# Intelligent_Agriculture.net
KiCad netlist of a schematic drawn in Altium Designer
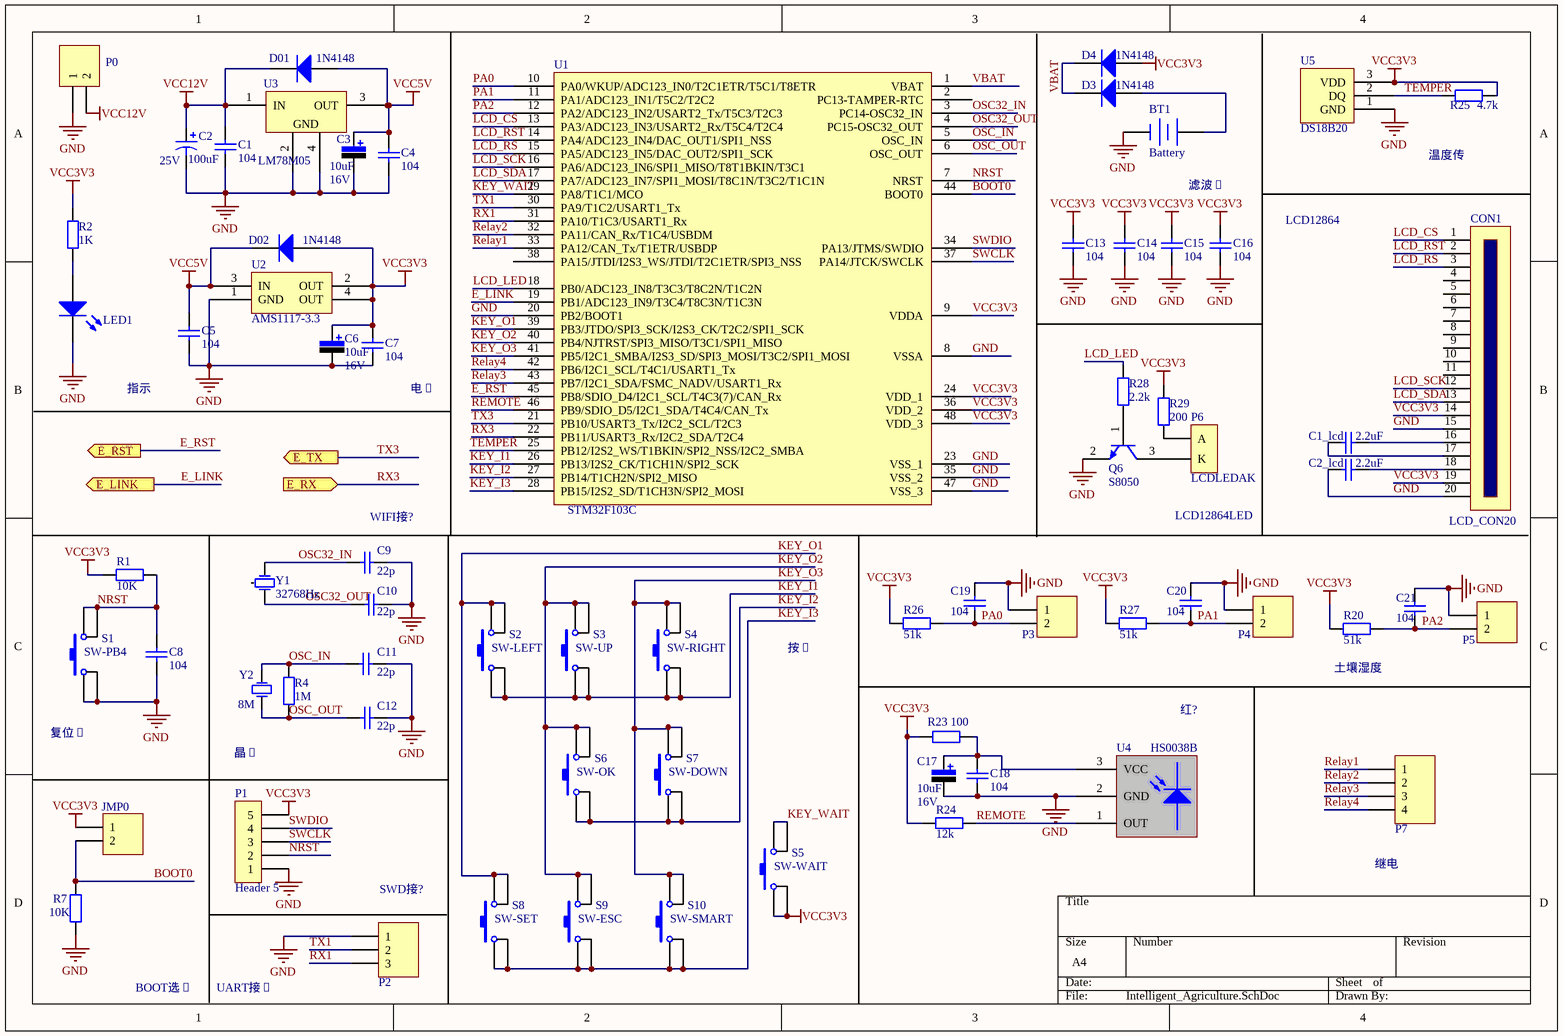
[diagram p0: Intelligent_Agriculture.SchDoc]

(export (version "E")
  (design (tool "Eeschema 10.0.6"))
  (components
    (comp (ref "BT1") (value "Battery") (description "备份电池") (libsource (lib "fszhang") (part "Battery")))
    (comp (ref "C1")
      (value "104")
      (footprint "C-RAD-0805")
      (description "无极性电容")
      (fields (field (name "Comment") "Cap"))
      (libsource (lib "Intelligent_Agriculture_Lib") (part "Cap"))
    )
    (comp (ref "C1_lcd")
      (value "2.2uF")
      (footprint "C-RAD-0805")
      (description "无极性电容")
      (fields (field (name "Comment") "Cap"))
      (libsource (lib "Intelligent_Agriculture_Lib") (part "Cap"))
    )
    (comp (ref "C2")
      (value "100uF")
      (footprint "C-RB-2.54")
      (description "电解电容")
      (fields (field (name "VOL") "25V") (field (name "Comment") "Cap Pol1"))
      (libsource (lib "Miscellaneous Devices") (part "Cap Pol1"))
    )
    (comp (ref "C2_lcd")
      (value "2.2uF")
      (footprint "C-RAD-0805")
      (description "无极性电容")
      (fields (field (name "Comment") "Cap"))
      (libsource (lib "Intelligent_Agriculture_Lib") (part "Cap"))
    )
    (comp (ref "C3")
      (value "10uF")
      (footprint "CAP-3528")
      (description "钽电容")
      (fields (field (name "VOL") "16V") (field (name "Comment") "Cap Pol"))
      (libsource (lib "Intelligent_Agriculture_Lib") (part "Cap Pol"))
    )
    (comp (ref "C4")
      (value "104")
      (footprint "C-RAD-0805")
      (description "无极性电容")
      (fields (field (name "Comment") "Cap"))
      (libsource (lib "Intelligent_Agriculture_Lib") (part "Cap"))
    )
    (comp (ref "C5")
      (value "104")
      (footprint "C-RAD-0805")
      (description "无极性电容")
      (fields (field (name "Comment") "Cap"))
      (libsource (lib "Intelligent_Agriculture_Lib") (part "Cap"))
    )
    (comp (ref "C6")
      (value "10uF")
      (footprint "CAP-3528")
      (description "钽电容")
      (fields (field (name "VOL") "16V") (field (name "Comment") "Cap Pol"))
      (libsource (lib "Intelligent_Agriculture_Lib") (part "Cap Pol"))
    )
    (comp (ref "C7")
      (value "104")
      (footprint "C-RAD-0805")
      (description "无极性电容")
      (fields (field (name "Comment") "Cap"))
      (libsource (lib "Intelligent_Agriculture_Lib") (part "Cap"))
    )
    (comp (ref "C8")
      (value "104")
      (footprint "C-RAD-0805")
      (description "无极性电容")
      (fields (field (name "Comment") "Cap"))
      (libsource (lib "Intelligent_Agriculture_Lib") (part "Cap"))
    )
    (comp (ref "C9")
      (value "22p")
      (footprint "C-RAD-0805")
      (description "无极性电容")
      (fields (field (name "Comment") "Cap"))
      (libsource (lib "Intelligent_Agriculture_Lib") (part "Cap"))
    )
    (comp (ref "C10")
      (value "22p")
      (footprint "C-RAD-0805")
      (description "无极性电容")
      (fields (field (name "Comment") "Cap"))
      (libsource (lib "Intelligent_Agriculture_Lib") (part "Cap"))
    )
    (comp (ref "C11")
      (value "22p")
      (footprint "C-RAD-0805")
      (description "无极性电容")
      (fields (field (name "Comment") "Cap"))
      (libsource (lib "Intelligent_Agriculture_Lib") (part "Cap"))
    )
    (comp (ref "C12")
      (value "22p")
      (footprint "C-RAD-0805")
      (description "无极性电容")
      (fields (field (name "Comment") "Cap"))
      (libsource (lib "Intelligent_Agriculture_Lib") (part "Cap"))
    )
    (comp (ref "C13")
      (value "104")
      (footprint "C-RAD-0805")
      (description "无极性电容")
      (fields (field (name "Comment") "Cap"))
      (libsource (lib "Intelligent_Agriculture_Lib") (part "Cap"))
    )
    (comp (ref "C14")
      (value "104")
      (footprint "C-RAD-0805")
      (description "无极性电容")
      (fields (field (name "Comment") "Cap"))
      (libsource (lib "Intelligent_Agriculture_Lib") (part "Cap"))
    )
    (comp (ref "C15")
      (value "104")
      (footprint "C-RAD-0805")
      (description "无极性电容")
      (fields (field (name "Comment") "Cap"))
      (libsource (lib "Intelligent_Agriculture_Lib") (part "Cap"))
    )
    (comp (ref "C16")
      (value "104")
      (footprint "C-RAD-0805")
      (description "无极性电容")
      (fields (field (name "Comment") "Cap"))
      (libsource (lib "Intelligent_Agriculture_Lib") (part "Cap"))
    )
    (comp (ref "C17")
      (value "10uF")
      (footprint "CAP-3528")
      (description "钽电容")
      (fields (field (name "VOL") "16V") (field (name "Comment") "Cap Pol"))
      (libsource (lib "Intelligent_Agriculture_Lib") (part "Cap Pol"))
    )
    (comp (ref "C18")
      (value "104")
      (footprint "C-RAD-0805")
      (description "无极性电容")
      (fields (field (name "Comment") "Cap"))
      (libsource (lib "Intelligent_Agriculture_Lib") (part "Cap"))
    )
    (comp (ref "C19")
      (value "104")
      (footprint "C-RAD-0805")
      (description "无极性电容")
      (fields (field (name "Comment") "Cap"))
      (libsource (lib "Intelligent_Agriculture_Lib") (part "Cap"))
    )
    (comp (ref "C20")
      (value "104")
      (footprint "C-RAD-0805")
      (description "无极性电容")
      (fields (field (name "Comment") "Cap"))
      (libsource (lib "Intelligent_Agriculture_Lib") (part "Cap"))
    )
    (comp (ref "C21")
      (value "104")
      (footprint "C-RAD-0805")
      (description "无极性电容")
      (fields (field (name "Comment") "Cap"))
      (libsource (lib "Intelligent_Agriculture_Lib") (part "Cap"))
    )
    (comp (ref "CON1")
      (value "LCD_CON20")
      (footprint "FPC0.5-20P-A")
      (description "LCD接插件")
      (libsource (lib "fszhang") (part "LCD_CON20"))
    )
    (comp (ref "D01")
      (value "1N4148")
      (footprint "DIODE-1206")
      (description "二极管")
      (fields (field (name "Comment") "Diode"))
      (libsource (lib "Intelligent_Agriculture_Lib") (part "Diode"))
    )
    (comp (ref "D02")
      (value "1N4148")
      (footprint "DIODE-1206")
      (description "二极管")
      (fields (field (name "Comment") "Diode"))
      (libsource (lib "Intelligent_Agriculture_Lib") (part "Diode"))
    )
    (comp (ref "D3")
      (value "1N4148")
      (footprint "DIODE-1206")
      (description "二极管")
      (fields (field (name "Comment") "Diode"))
      (libsource (lib "Intelligent_Agriculture_Lib") (part "Diode"))
    )
    (comp (ref "D4")
      (value "1N4148")
      (footprint "DIODE-1206")
      (description "二极管")
      (fields (field (name "Comment") "Diode"))
      (libsource (lib "Intelligent_Agriculture_Lib") (part "Diode"))
    )
    (comp (ref "JMP0")
      (value "Header 2")
      (footprint "HDR2X1_A")
      (description "接插件")
      (libsource (lib "fszhang") (part "Header 2"))
    )
    (comp (ref "LED1")
      (value "LED0")
      (footprint "LED_A2")
      (description "发光二极管")
      (libsource (lib "Intelligent_Agriculture_Lib") (part "LED0"))
    )
    (comp (ref "P0")
      (value "Header 2")
      (footprint "HDR2X1_B1")
      (description "接插件")
      (libsource (lib "") (part "Header 2_1"))
    )
    (comp (ref "P1")
      (value "Header 5")
      (footprint "HDR5_A1")
      (description "接插件")
      (libsource (lib "fszhang") (part "Header 5"))
    )
    (comp (ref "P2")
      (value "Header 3")
      (footprint "HDR3X1_A")
      (description "接插件")
      (libsource (lib "fszhang") (part "Header 3"))
    )
    (comp (ref "P3")
      (value "Header 2")
      (footprint "HDR2X1_B1")
      (description "接插件")
      (libsource (lib "fszhang") (part "Header 2"))
    )
    (comp (ref "P4")
      (value "Header 2")
      (footprint "HDR2X1_B1")
      (description "接插件")
      (libsource (lib "fszhang") (part "Header 2"))
    )
    (comp (ref "P5")
      (value "Header 2")
      (footprint "HDR2X1_B1")
      (description "接插件")
      (libsource (lib "fszhang") (part "Header 2"))
    )
    (comp (ref "P6")
      (value "LCDLEDAK")
      (footprint "LCD_JLX12864G-1504")
      (description "LCD12864框架")
      (libsource (lib "fszhang") (part "LCDLEDAK"))
    )
    (comp (ref "P7")
      (value "Header 4")
      (footprint "HDR4X1_B1")
      (description "接插件")
      (libsource (lib "fszhang") (part "Header 4"))
    )
    (comp (ref "Q6") (value "S8050") (description "NPN三极管") (libsource (lib "fszhang") (part "BCP68")))
    (comp (ref "R1")
      (value "10K")
      (description "贴片电阻")
      (fields (field (name "Comment") "Res1"))
      (libsource (lib "fszhang") (part "Res1"))
    )
    (comp (ref "R2")
      (value "1K")
      (description "贴片电阻")
      (fields (field (name "Comment") "Res1"))
      (libsource (lib "") (part "Res1_1"))
    )
    (comp (ref "R4")
      (value "1M")
      (description "贴片电阻")
      (fields (field (name "Comment") "Res1"))
      (libsource (lib "") (part "Res1_1"))
    )
    (comp (ref "R7")
      (value "10K")
      (description "贴片电阻")
      (fields (field (name "Comment") "Res1"))
      (libsource (lib "") (part "Res1_2"))
    )
    (comp (ref "R20")
      (value "51k")
      (description "贴片电阻")
      (fields (field (name "Comment") "Res1"))
      (libsource (lib "fszhang") (part "Res1"))
    )
    (comp (ref "R23")
      (value "100")
      (description "贴片电阻")
      (fields (field (name "Comment") "Res1"))
      (libsource (lib "") (part "Res1_3"))
    )
    (comp (ref "R24")
      (value "12k")
      (description "贴片电阻")
      (fields (field (name "Comment") "Res1"))
      (libsource (lib "") (part "Res1_3"))
    )
    (comp (ref "R25")
      (value "4.7k")
      (description "贴片电阻")
      (fields (field (name "Comment") "Res1"))
      (libsource (lib "") (part "Res1_3"))
    )
    (comp (ref "R26")
      (value "51k")
      (description "贴片电阻")
      (fields (field (name "Comment") "Res1"))
      (libsource (lib "fszhang") (part "Res1"))
    )
    (comp (ref "R27")
      (value "51k")
      (description "贴片电阻")
      (fields (field (name "Comment") "Res1"))
      (libsource (lib "fszhang") (part "Res1"))
    )
    (comp (ref "R28")
      (value "2.2k")
      (description "贴片电阻")
      (fields (field (name "Comment") "Res1"))
      (libsource (lib "") (part "Res1_1"))
    )
    (comp (ref "R29")
      (value "200")
      (footprint "1206")
      (description "贴片电阻")
      (fields (field (name "Comment") "Res1"))
      (libsource (lib "") (part "Res1_1"))
    )
    (comp (ref "S1")
      (value "SW-PB4")
      (footprint "SW_PB4_B1")
      (description "微动开关")
      (libsource (lib "fszhang") (part "SW-PB4"))
    )
    (comp (ref "S2")
      (value "SW-LEFT")
      (footprint "SW_PB4_B1")
      (description "微动开关")
      (libsource (lib "fszhang") (part "SW-PB4"))
    )
    (comp (ref "S3")
      (value "SW-UP")
      (footprint "SW_PB4_B1")
      (description "微动开关")
      (libsource (lib "fszhang") (part "SW-PB4"))
    )
    (comp (ref "S4")
      (value "SW-RIGHT")
      (footprint "SW_PB4_B1")
      (description "微动开关")
      (libsource (lib "fszhang") (part "SW-PB4"))
    )
    (comp (ref "S5")
      (value "SW-WAIT")
      (footprint "SW_PB4_B1")
      (description "微动开关")
      (libsource (lib "fszhang") (part "SW-PB4"))
    )
    (comp (ref "S6")
      (value "SW-OK")
      (footprint "SW_PB4_B1")
      (description "微动开关")
      (libsource (lib "fszhang") (part "SW-PB4"))
    )
    (comp (ref "S7")
      (value "SW-DOWN")
      (footprint "SW_PB4_B1")
      (description "微动开关")
      (libsource (lib "fszhang") (part "SW-PB4"))
    )
    (comp (ref "S8")
      (value "SW-SET")
      (footprint "SW_PB4_B1")
      (description "微动开关")
      (libsource (lib "fszhang") (part "SW-PB4"))
    )
    (comp (ref "S9")
      (value "SW-ESC")
      (footprint "SW_PB4_B1")
      (description "微动开关")
      (libsource (lib "fszhang") (part "SW-PB4"))
    )
    (comp (ref "S10")
      (value "SW-SMART")
      (footprint "SW_PB4_B1")
      (description "微动开关")
      (libsource (lib "fszhang") (part "SW-PB4"))
    )
    (comp (ref "U1")
      (value "STM32F103C")
      (footprint "LQFP-48_M")
      (description "STM32单片机48引脚")
      (libsource (lib "fszhang") (part "STM32F103C"))
    )
    (comp (ref "U2")
      (value "AMS1117-3.3")
      (footprint "SOT-223")
      (description "3.3V稳压芯片")
      (libsource (lib "fszhang") (part "SPX1117M3-3.3"))
    )
    (comp (ref "U3")
      (value "LM78M05")
      (footprint "TO-252")
      (description "5V稳压芯片")
      (libsource (lib "fszhang") (part "LM78M05"))
    )
    (comp (ref "U4")
      (value "HS0038B")
      (description "红外接收器")
      (libsource (lib "fszhang") (part "HS0038B"))
    )
    (comp (ref "U5")
      (value "DS18B20")
      (footprint "HDR3X1_B1")
      (description "温度传感器")
      (libsource (lib "fszhang") (part "DS18B20"))
    )
    (comp (ref "Y1")
      (value "32768Hz")
      (footprint "X-TC15_B")
      (description "圆柱晶振")
      (fields (field (name "Comment") "XTAL_SM"))
      (libsource (lib "Intelligent_Agriculture_Lib") (part "XTAL_SM"))
    )
    (comp (ref "Y2")
      (value "8M")
      (description "晶振")
      (fields (field (name "Comment") "XTAL"))
      (libsource (lib "fszhang") (part "XTAL"))
    )
  )
  (nets
    (net (code "1") (name "/BOOT0") (class "Default")
      (node (ref "JMP0") (pin "2") (pinfunction "2_2") (pintype "passive"))
      (node (ref "R7") (pin "1") (pinfunction "1_1") (pintype "passive"))
      (node (ref "U1") (pin "44") (pinfunction "BOOT0_44") (pintype "passive"))
    )
    (net (code "2") (name "/E_LINK") (class "Default")
      (node (ref "U1") (pin "19") (pinfunction "PB1/ADC123_IN9/T3C4/T8C3N/T1C3N_19") (pintype "passive"))
    )
    (net (code "3") (name "/E_RST") (class "Default")
      (node (ref "U1") (pin "45") (pinfunction "PB8/SDIO_D4/I2C1_SCL/T4C3(7)/CAN_Rx_45") (pintype "passive"))
    )
    (net (code "4") (name "/KEY_I1") (class "Default")
      (node (ref "S2") (pin "1") (pinfunction "1_1") (pintype "passive"))
      (node (ref "S2") (pin "4") (pinfunction "4_4") (pintype "passive"))
      (node (ref "S3") (pin "1") (pinfunction "1_1") (pintype "passive"))
      (node (ref "S3") (pin "4") (pinfunction "4_4") (pintype "passive"))
      (node (ref "S4") (pin "1") (pinfunction "1_1") (pintype "passive"))
      (node (ref "S4") (pin "4") (pinfunction "4_4") (pintype "passive"))
      (node (ref "U1") (pin "26") (pinfunction "PB13/I2S2_CK/T1CH1N/SPI2_SCK_26") (pintype "passive"))
    )
    (net (code "5") (name "/KEY_I2") (class "Default")
      (node (ref "S6") (pin "1") (pinfunction "1_1") (pintype "passive"))
      (node (ref "S6") (pin "4") (pinfunction "4_4") (pintype "passive"))
      (node (ref "S7") (pin "1") (pinfunction "1_1") (pintype "passive"))
      (node (ref "S7") (pin "4") (pinfunction "4_4") (pintype "passive"))
      (node (ref "U1") (pin "27") (pinfunction "PB14/T1CH2N/SPI2_MISO_27") (pintype "passive"))
    )
    (net (code "6") (name "/KEY_I3") (class "Default")
      (node (ref "S10") (pin "1") (pinfunction "1_1") (pintype "passive"))
      (node (ref "S10") (pin "4") (pinfunction "4_4") (pintype "passive"))
      (node (ref "S8") (pin "1") (pinfunction "1_1") (pintype "passive"))
      (node (ref "S8") (pin "4") (pinfunction "4_4") (pintype "passive"))
      (node (ref "S9") (pin "1") (pinfunction "1_1") (pintype "passive"))
      (node (ref "S9") (pin "4") (pinfunction "4_4") (pintype "passive"))
      (node (ref "U1") (pin "28") (pinfunction "PB15/I2S2_SD/T1CH3N/SPI2_MOSI_28") (pintype "passive"))
    )
    (net (code "7") (name "/KEY_O1") (class "Default")
      (node (ref "S2") (pin "2") (pinfunction "2_2") (pintype "passive"))
      (node (ref "S2") (pin "3") (pinfunction "3_3") (pintype "passive"))
      (node (ref "S8") (pin "2") (pinfunction "2_2") (pintype "passive"))
      (node (ref "S8") (pin "3") (pinfunction "3_3") (pintype "passive"))
      (node (ref "U1") (pin "39") (pinfunction "PB3/JTDO/SPI3_SCK/I2S3_CK/T2C2/SPI1_SCK_39") (pintype "passive"))
    )
    (net (code "8") (name "/KEY_O2") (class "Default")
      (node (ref "S3") (pin "2") (pinfunction "2_2") (pintype "passive"))
      (node (ref "S3") (pin "3") (pinfunction "3_3") (pintype "passive"))
      (node (ref "S6") (pin "2") (pinfunction "2_2") (pintype "passive"))
      (node (ref "S6") (pin "3") (pinfunction "3_3") (pintype "passive"))
      (node (ref "S9") (pin "2") (pinfunction "2_2") (pintype "passive"))
      (node (ref "S9") (pin "3") (pinfunction "3_3") (pintype "passive"))
      (node (ref "U1") (pin "40") (pinfunction "PB4/NJTRST/SPI3_MISO/T3C1/SPI1_MISO_40") (pintype "passive"))
    )
    (net (code "9") (name "/KEY_O3") (class "Default")
      (node (ref "S10") (pin "2") (pinfunction "2_2") (pintype "passive"))
      (node (ref "S10") (pin "3") (pinfunction "3_3") (pintype "passive"))
      (node (ref "S4") (pin "2") (pinfunction "2_2") (pintype "passive"))
      (node (ref "S4") (pin "3") (pinfunction "3_3") (pintype "passive"))
      (node (ref "S7") (pin "2") (pinfunction "2_2") (pintype "passive"))
      (node (ref "S7") (pin "3") (pinfunction "3_3") (pintype "passive"))
      (node (ref "U1") (pin "41") (pinfunction "PB5/I2C1_SMBA/I2S3_SD/SPI3_MOSI/T3C2/SPI1_MOSI_41") (pintype "passive"))
    )
    (net (code "10") (name "/KEY_WAIT") (class "Default")
      (node (ref "S5") (pin "2") (pinfunction "2_2") (pintype "passive"))
      (node (ref "S5") (pin "3") (pinfunction "3_3") (pintype "passive"))
      (node (ref "U1") (pin "29") (pinfunction "PA8/T1C1/MCO_29") (pintype "passive"))
    )
    (net (code "11") (name "/LCD_CS") (class "Default")
      (node (ref "CON1") (pin "1") (pinfunction "1_1") (pintype "passive"))
      (node (ref "U1") (pin "13") (pinfunction "PA3/ADC123_IN3/USART2_Rx/T5C4/T2C4_13") (pintype "passive"))
    )
    (net (code "12") (name "/LCD_LED") (class "Default")
      (node (ref "R28") (pin "2") (pinfunction "2_2") (pintype "passive"))
      (node (ref "U1") (pin "18") (pinfunction "PB0/ADC123_IN8/T3C3/T8C2N/T1C2N_18") (pintype "passive"))
    )
    (net (code "13") (name "/LCD_RS") (class "Default")
      (node (ref "CON1") (pin "3") (pinfunction "3_3") (pintype "passive"))
      (node (ref "U1") (pin "15") (pinfunction "PA5/ADC123_IN5/DAC_OUT2/SPI1_SCK_15") (pintype "passive"))
    )
    (net (code "14") (name "/LCD_RST") (class "Default")
      (node (ref "CON1") (pin "2") (pinfunction "2_2") (pintype "passive"))
      (node (ref "U1") (pin "14") (pinfunction "PA4/ADC123_IN4/DAC_OUT1/SPI1_NSS_14") (pintype "passive"))
    )
    (net (code "15") (name "/LCD_SCK") (class "Default")
      (node (ref "CON1") (pin "12") (pinfunction "12_12") (pintype "passive"))
      (node (ref "U1") (pin "16") (pinfunction "PA6/ADC123_IN6/SPI1_MISO/T8T1BKIN/T3C1_16") (pintype "passive"))
    )
    (net (code "16") (name "/LCD_SDA") (class "Default")
      (node (ref "CON1") (pin "13") (pinfunction "13_13") (pintype "passive"))
      (node (ref "U1") (pin "17") (pinfunction "PA7/ADC123_IN7/SPI1_MOSI/T8C1N/T3C2/T1C1N_17") (pintype "passive"))
    )
    (net (code "17") (name "/NRST") (class "Default")
      (node (ref "C8") (pin "2") (pinfunction "2_2") (pintype "passive"))
      (node (ref "P1") (pin "2") (pinfunction "2_2") (pintype "passive"))
      (node (ref "R1") (pin "1") (pinfunction "1_1") (pintype "passive"))
      (node (ref "S1") (pin "2") (pinfunction "2_2") (pintype "passive"))
      (node (ref "S1") (pin "3") (pinfunction "3_3") (pintype "passive"))
      (node (ref "U1") (pin "7") (pinfunction "NRST_7") (pintype "passive"))
    )
    (net (code "18") (name "/OSC32_IN") (class "Default")
      (node (ref "C9") (pin "1") (pinfunction "1_1") (pintype "passive"))
      (node (ref "U1") (pin "3") (pinfunction "PC14-OSC32_IN_3") (pintype "passive"))
      (node (ref "Y1") (pin "1") (pinfunction "OSC1_1") (pintype "passive"))
    )
    (net (code "19") (name "/OSC32_OUT") (class "Default")
      (node (ref "C10") (pin "1") (pinfunction "1_1") (pintype "passive"))
      (node (ref "U1") (pin "4") (pinfunction "PC15-OSC32_OUT_4") (pintype "passive"))
      (node (ref "Y1") (pin "2") (pinfunction "OSC2_2") (pintype "passive"))
    )
    (net (code "20") (name "/OSC_IN") (class "Default")
      (node (ref "C11") (pin "1") (pinfunction "1_1") (pintype "passive"))
      (node (ref "R4") (pin "2") (pinfunction "2_2") (pintype "passive"))
      (node (ref "U1") (pin "5") (pinfunction "OSC_IN_5") (pintype "passive"))
      (node (ref "Y2") (pin "2") (pinfunction "OSC2_2") (pintype "passive"))
    )
    (net (code "21") (name "/OSC_OUT") (class "Default")
      (node (ref "C12") (pin "1") (pinfunction "1_1") (pintype "passive"))
      (node (ref "R4") (pin "1") (pinfunction "1_1") (pintype "passive"))
      (node (ref "U1") (pin "6") (pinfunction "OSC_OUT_6") (pintype "passive"))
      (node (ref "Y2") (pin "1") (pinfunction "OSC1_1") (pintype "passive"))
    )
    (net (code "22") (name "/PA0") (class "Default")
      (node (ref "C19") (pin "2") (pinfunction "2_2") (pintype "passive"))
      (node (ref "P3") (pin "2") (pinfunction "2_2") (pintype "passive"))
      (node (ref "R26") (pin "1") (pinfunction "1_1") (pintype "passive"))
      (node (ref "U1") (pin "10") (pinfunction "PA0/WKUP/ADC123_IN0/T2C1ETR/T5C1/T8ETR_10") (pintype "passive"))
    )
    (net (code "23") (name "/PA1") (class "Default")
      (node (ref "C20") (pin "2") (pinfunction "2_2") (pintype "passive"))
      (node (ref "P4") (pin "2") (pinfunction "2_2") (pintype "passive"))
      (node (ref "R27") (pin "1") (pinfunction "1_1") (pintype "passive"))
      (node (ref "U1") (pin "11") (pinfunction "PA1/ADC123_IN1/T5C2/T2C2_11") (pintype "passive"))
    )
    (net (code "24") (name "/PA2") (class "Default")
      (node (ref "C21") (pin "2") (pinfunction "2_2") (pintype "passive"))
      (node (ref "P5") (pin "2") (pinfunction "2_2") (pintype "passive"))
      (node (ref "R20") (pin "1") (pinfunction "1_1") (pintype "passive"))
      (node (ref "U1") (pin "12") (pinfunction "PA2/ADC123_IN2/USART2_Tx/T5C3/T2C3_12") (pintype "passive"))
    )
    (net (code "25") (name "/REMOTE") (class "Default")
      (node (ref "R24") (pin "2") (pinfunction "2_2") (pintype "passive"))
      (node (ref "U1") (pin "46") (pinfunction "PB9/SDIO_D5/I2C1_SDA/T4C4/CAN_Tx_46") (pintype "passive"))
      (node (ref "U4") (pin "1") (pinfunction "OUT_1") (pintype "passive"))
    )
    (net (code "26") (name "/RX1") (class "Default")
      (node (ref "P2") (pin "3") (pinfunction "3_3") (pintype "passive"))
      (node (ref "U1") (pin "31") (pinfunction "PA10/T1C3/USART1_Rx_31") (pintype "passive"))
    )
    (net (code "27") (name "/RX3") (class "Default")
      (node (ref "U1") (pin "22") (pinfunction "PB11/USART3_Rx/I2C2_SDA/T2C4_22") (pintype "passive"))
    )
    (net (code "28") (name "/Relay1") (class "Default")
      (node (ref "P7") (pin "1") (pinfunction "1_1") (pintype "passive"))
      (node (ref "U1") (pin "33") (pinfunction "PA12/CAN_Tx/T1ETR/USBDP_33") (pintype "passive"))
    )
    (net (code "29") (name "/Relay2") (class "Default")
      (node (ref "P7") (pin "2") (pinfunction "2_2") (pintype "passive"))
      (node (ref "U1") (pin "32") (pinfunction "PA11/CAN_Rx/T1C4/USBDM_32") (pintype "passive"))
    )
    (net (code "30") (name "/Relay3") (class "Default")
      (node (ref "P7") (pin "3") (pinfunction "3_3") (pintype "passive"))
      (node (ref "U1") (pin "43") (pinfunction "PB7/I2C1_SDA/FSMC_NADV/USART1_Rx_43") (pintype "passive"))
    )
    (net (code "31") (name "/Relay4") (class "Default")
      (node (ref "P7") (pin "4") (pinfunction "4_4") (pintype "passive"))
      (node (ref "U1") (pin "42") (pinfunction "PB6/I2C1_SCL/T4C1/USART1_Tx_42") (pintype "passive"))
    )
    (net (code "32") (name "/SWCLK") (class "Default")
      (node (ref "P1") (pin "3") (pinfunction "3_3") (pintype "passive"))
      (node (ref "U1") (pin "37") (pinfunction "PA14/JTCK/SWCLK_37") (pintype "passive"))
    )
    (net (code "33") (name "/SWDIO") (class "Default")
      (node (ref "P1") (pin "4") (pinfunction "4_4") (pintype "passive"))
      (node (ref "U1") (pin "34") (pinfunction "PA13/JTMS/SWDIO_34") (pintype "passive"))
    )
    (net (code "34") (name "/TEMPER") (class "Default")
      (node (ref "R25") (pin "1") (pinfunction "1_1") (pintype "passive"))
      (node (ref "U1") (pin "25") (pinfunction "PB12/I2S2_WS/T1BKIN/SPI2_NSS/I2C2_SMBA_25") (pintype "passive"))
      (node (ref "U5") (pin "2") (pinfunction "DQ_2") (pintype "passive"))
    )
    (net (code "35") (name "/TX1") (class "Default")
      (node (ref "P2") (pin "2") (pinfunction "2_2") (pintype "passive"))
      (node (ref "U1") (pin "30") (pinfunction "PA9/T1C2/USART1_Tx_30") (pintype "passive"))
    )
    (net (code "36") (name "/TX3") (class "Default")
      (node (ref "U1") (pin "21") (pinfunction "PB10/USART3_Tx/I2C2_SCL/T2C3_21") (pintype "passive"))
    )
    (net (code "37") (name "/VBAT") (class "Default")
      (node (ref "D3") (pin "2") (pinfunction "K_2") (pintype "passive"))
      (node (ref "D4") (pin "2") (pinfunction "K_2") (pintype "passive"))
      (node (ref "U1") (pin "1") (pinfunction "VBAT_1") (pintype "passive"))
    )
    (net (code "38") (name "GND") (class "Default")
      (node (ref "BT1") (pin "2") (pinfunction "-_2") (pintype "passive"))
      (node (ref "C1") (pin "2") (pinfunction "2_2") (pintype "passive"))
      (node (ref "C10") (pin "2") (pinfunction "2_2") (pintype "passive"))
      (node (ref "C11") (pin "2") (pinfunction "2_2") (pintype "passive"))
      (node (ref "C12") (pin "2") (pinfunction "2_2") (pintype "passive"))
      (node (ref "C13") (pin "2") (pinfunction "2_2") (pintype "passive"))
      (node (ref "C14") (pin "2") (pinfunction "2_2") (pintype "passive"))
      (node (ref "C15") (pin "2") (pinfunction "2_2") (pintype "passive"))
      (node (ref "C16") (pin "2") (pinfunction "2_2") (pintype "passive"))
      (node (ref "C17") (pin "2") (pinfunction "2_2") (pintype "passive"))
      (node (ref "C18") (pin "2") (pinfunction "2_2") (pintype "passive"))
      (node (ref "C19") (pin "1") (pinfunction "1_1") (pintype "passive"))
      (node (ref "C2") (pin "2") (pinfunction "2_2") (pintype "passive"))
      (node (ref "C20") (pin "1") (pinfunction "1_1") (pintype "passive"))
      (node (ref "C21") (pin "1") (pinfunction "1_1") (pintype "passive"))
      (node (ref "C2_lcd") (pin "2") (pinfunction "2_2") (pintype "passive"))
      (node (ref "C3") (pin "2") (pinfunction "2_2") (pintype "passive"))
      (node (ref "C4") (pin "2") (pinfunction "2_2") (pintype "passive"))
      (node (ref "C5") (pin "2") (pinfunction "2_2") (pintype "passive"))
      (node (ref "C6") (pin "2") (pinfunction "2_2") (pintype "passive"))
      (node (ref "C7") (pin "2") (pinfunction "2_2") (pintype "passive"))
      (node (ref "C8") (pin "1") (pinfunction "1_1") (pintype "passive"))
      (node (ref "C9") (pin "2") (pinfunction "2_2") (pintype "passive"))
      (node (ref "CON1") (pin "15") (pinfunction "15_15") (pintype "passive"))
      (node (ref "CON1") (pin "20") (pinfunction "20_20") (pintype "passive"))
      (node (ref "LED1") (pin "2") (pinfunction "K_2") (pintype "passive"))
      (node (ref "P0") (pin "1") (pinfunction "1_1") (pintype "passive"))
      (node (ref "P1") (pin "1") (pinfunction "1_1") (pintype "passive"))
      (node (ref "P2") (pin "1") (pinfunction "1_1") (pintype "passive"))
      (node (ref "P3") (pin "1") (pinfunction "1_1") (pintype "passive"))
      (node (ref "P4") (pin "1") (pinfunction "1_1") (pintype "passive"))
      (node (ref "P5") (pin "1") (pinfunction "1_1") (pintype "passive"))
      (node (ref "Q6") (pin "2") (pinfunction "E_2") (pintype "passive"))
      (node (ref "R7") (pin "2") (pinfunction "2_2") (pintype "passive"))
      (node (ref "S1") (pin "1") (pinfunction "1_1") (pintype "passive"))
      (node (ref "S1") (pin "4") (pinfunction "4_4") (pintype "passive"))
      (node (ref "U1") (pin "20") (pinfunction "PB2/BOOT1_20") (pintype "passive"))
      (node (ref "U1") (pin "23") (pinfunction "VSS_1_23") (pintype "passive"))
      (node (ref "U1") (pin "35") (pinfunction "VSS_2_35") (pintype "passive"))
      (node (ref "U1") (pin "47") (pinfunction "VSS_3_47") (pintype "passive"))
      (node (ref "U1") (pin "8") (pinfunction "VSSA_8") (pintype "passive"))
      (node (ref "U2") (pin "1") (pinfunction "GND_1") (pintype "passive"))
      (node (ref "U3") (pin "2") (pinfunction "GND_2") (pintype "power_in"))
      (node (ref "U3") (pin "4") (pinfunction "GND_4") (pintype "power_in"))
      (node (ref "U4") (pin "2") (pinfunction "GND_2") (pintype "passive"))
      (node (ref "U5") (pin "1") (pinfunction "GND_1") (pintype "passive"))
    )
    (net (code "39") (name "Net-(BT1-+)") (class "Default")
      (node (ref "BT1") (pin "1") (pinfunction "+_1") (pintype "passive"))
      (node (ref "D3") (pin "1") (pinfunction "A_1") (pintype "passive"))
    )
    (net (code "40") (name "Net-(C1_lcd-Pad1)") (class "Default")
      (node (ref "C1_lcd") (pin "1") (pinfunction "1_1") (pintype "passive"))
      (node (ref "CON1") (pin "16") (pinfunction "16_16") (pintype "passive"))
    )
    (net (code "41") (name "Net-(C1_lcd-Pad2)") (class "Default")
      (node (ref "C1_lcd") (pin "2") (pinfunction "2_2") (pintype "passive"))
      (node (ref "CON1") (pin "17") (pinfunction "17_17") (pintype "passive"))
    )
    (net (code "42") (name "Net-(C2_lcd-Pad1)") (class "Default")
      (node (ref "C2_lcd") (pin "1") (pinfunction "1_1") (pintype "passive"))
      (node (ref "CON1") (pin "18") (pinfunction "18_18") (pintype "passive"))
    )
    (net (code "43") (name "Net-(LED1-A)") (class "Default")
      (node (ref "LED1") (pin "1") (pinfunction "A_1") (pintype "passive"))
      (node (ref "R2") (pin "1") (pinfunction "1_1") (pintype "passive"))
    )
    (net (code "44") (name "Net-(P6-A)") (class "Default")
      (node (ref "P6") (pin "1") (pinfunction "A_1") (pintype "passive"))
      (node (ref "R29") (pin "1") (pinfunction "1_1") (pintype "passive"))
    )
    (net (code "45") (name "Net-(P6-K)") (class "Default")
      (node (ref "P6") (pin "2") (pinfunction "K_2") (pintype "passive"))
      (node (ref "Q6") (pin "3") (pinfunction "C_3") (pintype "passive"))
    )
    (net (code "46") (name "Net-(Q6-B)") (class "Default")
      (node (ref "Q6") (pin "1") (pinfunction "B_1") (pintype "passive"))
      (node (ref "R28") (pin "1") (pinfunction "1_1") (pintype "passive"))
    )
    (net (code "47") (name "Net-(U4-VCC)") (class "Default")
      (node (ref "C17") (pin "1") (pinfunction "1_1") (pintype "passive"))
      (node (ref "C18") (pin "1") (pinfunction "1_1") (pintype "passive"))
      (node (ref "R23") (pin "2") (pinfunction "2_2") (pintype "passive"))
      (node (ref "U4") (pin "3") (pinfunction "VCC_3") (pintype "passive"))
    )
    (net (code "48") (name "VCC3V3") (class "Default")
      (node (ref "C13") (pin "1") (pinfunction "1_1") (pintype "passive"))
      (node (ref "C14") (pin "1") (pinfunction "1_1") (pintype "passive"))
      (node (ref "C15") (pin "1") (pinfunction "1_1") (pintype "passive"))
      (node (ref "C16") (pin "1") (pinfunction "1_1") (pintype "passive"))
      (node (ref "C6") (pin "1") (pinfunction "1_1") (pintype "passive"))
      (node (ref "C7") (pin "1") (pinfunction "1_1") (pintype "passive"))
      (node (ref "CON1") (pin "14") (pinfunction "14_14") (pintype "passive"))
      (node (ref "CON1") (pin "19") (pinfunction "19_19") (pintype "passive"))
      (node (ref "D02") (pin "1") (pinfunction "A_1") (pintype "passive"))
      (node (ref "D4") (pin "1") (pinfunction "A_1") (pintype "passive"))
      (node (ref "JMP0") (pin "1") (pinfunction "1_1") (pintype "passive"))
      (node (ref "P1") (pin "5") (pinfunction "5_5") (pintype "passive"))
      (node (ref "R1") (pin "2") (pinfunction "2_2") (pintype "passive"))
      (node (ref "R2") (pin "2") (pinfunction "2_2") (pintype "passive"))
      (node (ref "R20") (pin "2") (pinfunction "2_2") (pintype "passive"))
      (node (ref "R23") (pin "1") (pinfunction "1_1") (pintype "passive"))
      (node (ref "R24") (pin "1") (pinfunction "1_1") (pintype "passive"))
      (node (ref "R25") (pin "2") (pinfunction "2_2") (pintype "passive"))
      (node (ref "R26") (pin "2") (pinfunction "2_2") (pintype "passive"))
      (node (ref "R27") (pin "2") (pinfunction "2_2") (pintype "passive"))
      (node (ref "R29") (pin "2") (pinfunction "2_2") (pintype "passive"))
      (node (ref "S5") (pin "1") (pinfunction "1_1") (pintype "passive"))
      (node (ref "S5") (pin "4") (pinfunction "4_4") (pintype "passive"))
      (node (ref "U1") (pin "24") (pinfunction "VDD_1_24") (pintype "passive"))
      (node (ref "U1") (pin "36") (pinfunction "VDD_2_36") (pintype "passive"))
      (node (ref "U1") (pin "48") (pinfunction "VDD_3_48") (pintype "passive"))
      (node (ref "U1") (pin "9") (pinfunction "VDDA_9") (pintype "passive"))
      (node (ref "U2") (pin "2") (pinfunction "OUT_2") (pintype "passive"))
      (node (ref "U2") (pin "4") (pinfunction "OUT_4") (pintype "passive"))
      (node (ref "U5") (pin "3") (pinfunction "VDD_3") (pintype "passive"))
    )
    (net (code "49") (name "VCC5V") (class "Default")
      (node (ref "C3") (pin "1") (pinfunction "1_1") (pintype "passive"))
      (node (ref "C4") (pin "1") (pinfunction "1_1") (pintype "passive"))
      (node (ref "C5") (pin "1") (pinfunction "1_1") (pintype "passive"))
      (node (ref "D01") (pin "1") (pinfunction "A_1") (pintype "passive"))
      (node (ref "D02") (pin "2") (pinfunction "K_2") (pintype "passive"))
      (node (ref "U2") (pin "3") (pinfunction "IN_3") (pintype "passive"))
      (node (ref "U3") (pin "3") (pinfunction "OUT_3") (pintype "power_in"))
    )
    (net (code "50") (name "VCC12V") (class "Default")
      (node (ref "C1") (pin "1") (pinfunction "1_1") (pintype "passive"))
      (node (ref "C2") (pin "1") (pinfunction "1_1") (pintype "passive"))
      (node (ref "D01") (pin "2") (pinfunction "K_2") (pintype "passive"))
      (node (ref "P0") (pin "2") (pinfunction "2_2") (pintype "passive"))
      (node (ref "U3") (pin "1") (pinfunction "IN_1") (pintype "power_in"))
    )
    (net (code "51") (name "unconnected-(CON1-Pad4)") (class "Default")
      (node (ref "CON1") (pin "4") (pinfunction "4_4") (pintype "passive"))
    )
    (net (code "52") (name "unconnected-(CON1-Pad5)") (class "Default")
      (node (ref "CON1") (pin "5") (pinfunction "5_5") (pintype "passive"))
    )
    (net (code "53") (name "unconnected-(CON1-Pad6)") (class "Default")
      (node (ref "CON1") (pin "6") (pinfunction "6_6") (pintype "passive"))
    )
    (net (code "54") (name "unconnected-(CON1-Pad7)") (class "Default")
      (node (ref "CON1") (pin "7") (pinfunction "7_7") (pintype "passive"))
    )
    (net (code "55") (name "unconnected-(CON1-Pad8)") (class "Default")
      (node (ref "CON1") (pin "8") (pinfunction "8_8") (pintype "passive"))
    )
    (net (code "56") (name "unconnected-(CON1-Pad9)") (class "Default")
      (node (ref "CON1") (pin "9") (pinfunction "9_9") (pintype "passive"))
    )
    (net (code "57") (name "unconnected-(CON1-Pad10)") (class "Default")
      (node (ref "CON1") (pin "10") (pinfunction "10_10") (pintype "passive"))
    )
    (net (code "58") (name "unconnected-(CON1-Pad11)") (class "Default")
      (node (ref "CON1") (pin "11") (pinfunction "11_11") (pintype "passive"))
    )
    (net (code "59") (name "unconnected-(U1-PA15{slash}JTDI{slash}I2S3_WS{slash}JTDI{slash}T2C1ETR{slash}SPI3_NSS-Pad38)") (class "Default")
      (node (ref "U1") (pin "38") (pinfunction "PA15/JTDI/I2S3_WS/JTDI/T2C1ETR/SPI3_NSS_38") (pintype "passive"))
    )
    (net (code "60") (name "unconnected-(U1-PC13-TAMPER-RTC-Pad2)") (class "Default")
      (node (ref "U1") (pin "2") (pinfunction "PC13-TAMPER-RTC_2") (pintype "passive"))
    )
    (net (code "61") (name "unconnected-(Y1-Pad3)") (class "Default")
      (node (ref "Y1") (pin "3") (pinfunction "3_3") (pintype "passive"))
    )
  )
)
